# mic.net
KiCad netlist of a schematic drawn in Altium Designer
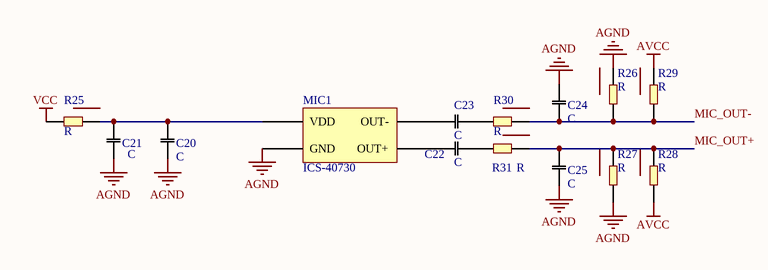
[diagram p0: mic.SchDoc]

(export (version "E")
  (design (tool "Eeschema 10.0.6"))
  (components
    (comp (ref "C20")
      (value "C")
      (footprint "402")
      (description "Capacitor")
      (libsource (lib "pass_comp") (part "C"))
    )
    (comp (ref "C21")
      (value "C")
      (footprint "402")
      (description "Capacitor")
      (libsource (lib "pass_comp") (part "C"))
    )
    (comp (ref "C22")
      (value "C")
      (footprint "402")
      (description "Capacitor")
      (libsource (lib "pass_comp") (part "C"))
    )
    (comp (ref "C23")
      (value "C")
      (footprint "402")
      (description "Capacitor")
      (libsource (lib "pass_comp") (part "C"))
    )
    (comp (ref "C24")
      (value "C")
      (footprint "402")
      (description "Capacitor")
      (libsource (lib "pass_comp") (part "C"))
    )
    (comp (ref "C25")
      (value "C")
      (footprint "402")
      (description "Capacitor")
      (libsource (lib "pass_comp") (part "C"))
    )
    (comp (ref "MIC1")
      (value "ICS-40730")
      (footprint "ICS-40730")
      (libsource (lib "env_sens") (part "ICS-40730"))
    )
    (comp (ref "R25")
      (value "R")
      (footprint "603")
      (description "Resistor")
      (libsource (lib "pass_comp") (part "R"))
    )
    (comp (ref "R26")
      (value "R")
      (footprint "402")
      (description "Resistor")
      (libsource (lib "") (part "R_1"))
    )
    (comp (ref "R27")
      (value "R")
      (footprint "402")
      (description "Resistor")
      (libsource (lib "") (part "R_1"))
    )
    (comp (ref "R28")
      (value "R")
      (footprint "402")
      (description "Resistor")
      (libsource (lib "") (part "R_1"))
    )
    (comp (ref "R29")
      (value "R")
      (footprint "402")
      (description "Resistor")
      (libsource (lib "") (part "R_1"))
    )
    (comp (ref "R30")
      (value "R")
      (footprint "402")
      (description "Resistor")
      (libsource (lib "pass_comp") (part "R"))
    )
    (comp (ref "R31")
      (value "R")
      (footprint "402")
      (description "Resistor")
      (libsource (lib "pass_comp") (part "R"))
    )
  )
  (nets
    (net (code "1") (name "/MIC_OUT+") (class "Default")
      (node (ref "C25") (pin "2") (pintype "passive"))
      (node (ref "R27") (pin "2") (pintype "passive"))
      (node (ref "R28") (pin "2") (pintype "passive"))
      (node (ref "R31") (pin "2") (pintype "passive"))
    )
    (net (code "2") (name "/MIC_OUT-") (class "Default")
      (node (ref "C24") (pin "1") (pintype "passive"))
      (node (ref "R26") (pin "1") (pintype "passive"))
      (node (ref "R29") (pin "1") (pintype "passive"))
      (node (ref "R30") (pin "2") (pintype "passive"))
    )
    (net (code "3") (name "AGND") (class "Default")
      (node (ref "C20") (pin "1") (pintype "passive"))
      (node (ref "C21") (pin "1") (pintype "passive"))
      (node (ref "C24") (pin "2") (pintype "passive"))
      (node (ref "C25") (pin "1") (pintype "passive"))
      (node (ref "MIC1") (pin "4") (pinfunction "GND_4") (pintype "passive"))
      (node (ref "R26") (pin "2") (pintype "passive"))
      (node (ref "R27") (pin "1") (pintype "passive"))
    )
    (net (code "4") (name "AVCC") (class "Default")
      (node (ref "R28") (pin "1") (pintype "passive"))
      (node (ref "R29") (pin "2") (pintype "passive"))
    )
    (net (code "5") (name "Net-(C22-Pad1)") (class "Default")
      (node (ref "C22") (pin "1") (pintype "passive"))
      (node (ref "R31") (pin "1") (pintype "passive"))
    )
    (net (code "6") (name "Net-(C23-Pad1)") (class "Default")
      (node (ref "C23") (pin "1") (pintype "passive"))
      (node (ref "R30") (pin "1") (pintype "passive"))
    )
    (net (code "7") (name "Net-(MIC1-OUT+)") (class "Default")
      (node (ref "C22") (pin "2") (pintype "passive"))
      (node (ref "MIC1") (pin "3") (pinfunction "OUT+_3") (pintype "passive"))
    )
    (net (code "8") (name "Net-(MIC1-OUT-)") (class "Default")
      (node (ref "C23") (pin "2") (pintype "passive"))
      (node (ref "MIC1") (pin "2") (pinfunction "OUT-_2") (pintype "passive"))
    )
    (net (code "9") (name "Net-(MIC1-VDD)") (class "Default")
      (node (ref "C20") (pin "2") (pintype "passive"))
      (node (ref "C21") (pin "2") (pintype "passive"))
      (node (ref "MIC1") (pin "1") (pinfunction "VDD_1") (pintype "passive"))
      (node (ref "R25") (pin "2") (pintype "passive"))
    )
    (net (code "10") (name "VCC") (class "Default") (node (ref "R25") (pin "1") (pintype "passive")))
  )
)
